# MiniDual_FanSpansion.net
KiCad netlist of a schematic drawn in EAGLE
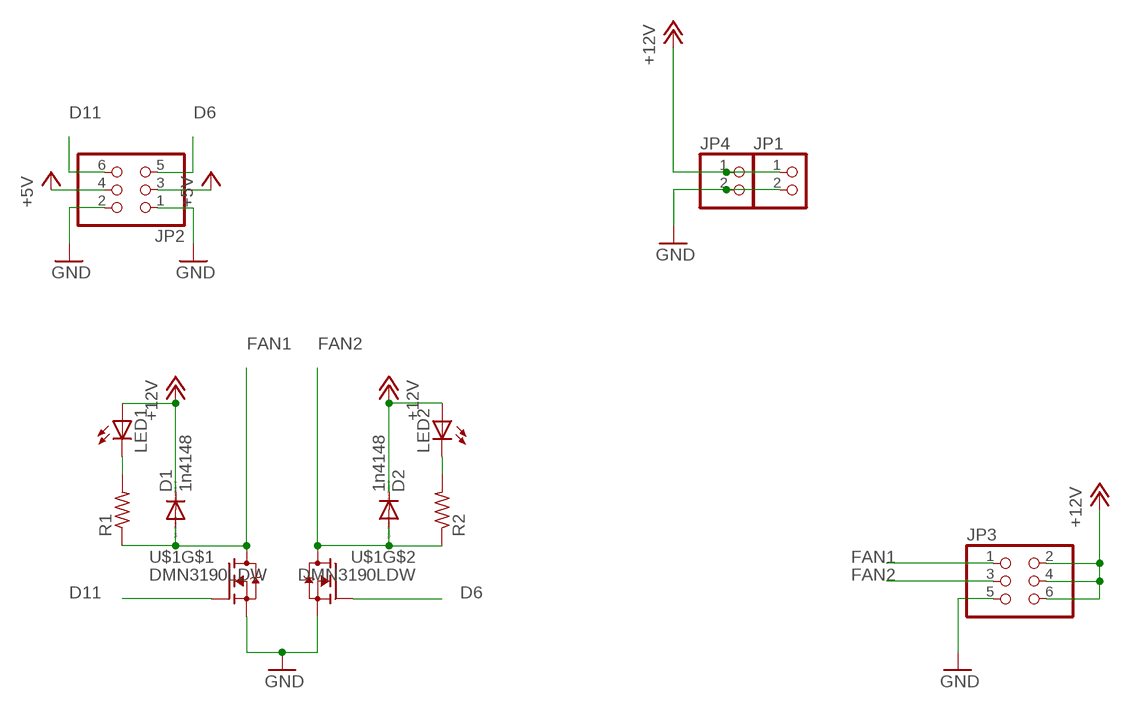
[diagram p0: schematic, sheet 1]

(export (version "E")
  (design (tool "Eeschema 10.0.6"))
  (components
    (comp (ref "D1")
      (value "1n4148")
      (footprint "eagle-import:SOD323-R")
      (libsource (lib "eagle-import") (part "DIODE-SOD323-R"))
    )
    (comp (ref "D2")
      (value "1n4148")
      (footprint "eagle-import:SOD323-R")
      (libsource (lib "eagle-import") (part "DIODE-SOD323-R"))
    )
    (comp (ref "JP1")
      (value "PINHD-1X2")
      (footprint "eagle-import:1X02")
      (libsource (lib "eagle-import") (part "PINHD-1X2"))
    )
    (comp (ref "JP2")
      (value "PINHD-2X3")
      (footprint "eagle-import:2X03")
      (libsource (lib "eagle-import") (part "PINHD-2X3"))
    )
    (comp (ref "JP3")
      (value "PINHD-2X3")
      (footprint "eagle-import:2X03")
      (libsource (lib "eagle-import") (part "PINHD-2X3"))
    )
    (comp (ref "JP4")
      (value "PINHD-1X2")
      (footprint "eagle-import:1X02")
      (libsource (lib "eagle-import") (part "PINHD-1X2"))
    )
    (comp (ref "LED1")
      (value "LEDSML0805")
      (footprint "eagle-import:SML0805")
      (libsource (lib "eagle-import") (part "LEDSML0805"))
    )
    (comp (ref "LED2")
      (value "LEDSML0805")
      (footprint "eagle-import:SML0805")
      (libsource (lib "eagle-import") (part "LEDSML0805"))
    )
    (comp (ref "R1")
      (value "R-US_R0805")
      (footprint "eagle-import:R0805")
      (libsource (lib "eagle-import") (part "R-US_R0805"))
    )
    (comp (ref "R2")
      (value "R-US_R0805")
      (footprint "eagle-import:R0805")
      (libsource (lib "eagle-import") (part "R-US_R0805"))
    )
    (comp (ref "U$1")
      (value "DMN3190LDW")
      (footprint "eagle-import:SOT65P210X110-6N")
      (libsource (lib "eagle-import") (part "DMN3190LDW"))
    )
  )
  (nets
    (net (code "1") (name "+5V") (class "Default")
      (node (ref "JP2") (pin "3") (pinfunction "3_3") (pintype "passive"))
      (node (ref "JP2") (pin "4") (pinfunction "4_4") (pintype "passive"))
    )
    (net (code "2") (name "+12V") (class "Default")
      (node (ref "D1") (pin "C") (pinfunction "C_C") (pintype "passive"))
      (node (ref "D2") (pin "C") (pinfunction "C_C") (pintype "passive"))
      (node (ref "JP1") (pin "1") (pinfunction "1_1") (pintype "passive"))
      (node (ref "JP3") (pin "2") (pinfunction "2_2") (pintype "passive"))
      (node (ref "JP3") (pin "4") (pinfunction "4_4") (pintype "passive"))
      (node (ref "JP3") (pin "6") (pinfunction "6_6") (pintype "passive"))
      (node (ref "JP4") (pin "1") (pinfunction "1_1") (pintype "passive"))
      (node (ref "LED1") (pin "A") (pinfunction "A_A") (pintype "passive"))
      (node (ref "LED2") (pin "A") (pinfunction "A_A") (pintype "passive"))
    )
    (net (code "3") (name "/D6") (class "Default")
      (node (ref "JP2") (pin "5") (pinfunction "5_5") (pintype "passive"))
      (node (ref "U$1") (pin "2") (pinfunction "G_2") (pintype "passive"))
    )
    (net (code "4") (name "/D11") (class "Default")
      (node (ref "JP2") (pin "6") (pinfunction "6_6") (pintype "passive"))
      (node (ref "U$1") (pin "5") (pinfunction "G_5") (pintype "passive"))
    )
    (net (code "5") (name "/FAN1") (class "Default")
      (node (ref "D1") (pin "A") (pinfunction "A_A") (pintype "passive"))
      (node (ref "JP3") (pin "1") (pinfunction "1_1") (pintype "passive"))
      (node (ref "R1") (pin "1") (pinfunction "1_1") (pintype "passive"))
      (node (ref "U$1") (pin "3") (pinfunction "D_3") (pintype "passive"))
    )
    (net (code "6") (name "/FAN2") (class "Default")
      (node (ref "D2") (pin "A") (pinfunction "A_A") (pintype "passive"))
      (node (ref "JP3") (pin "3") (pinfunction "3_3") (pintype "passive"))
      (node (ref "R2") (pin "1") (pinfunction "1_1") (pintype "passive"))
      (node (ref "U$1") (pin "6") (pinfunction "D_6") (pintype "passive"))
    )
    (net (code "7") (name "GND") (class "Default")
      (node (ref "JP1") (pin "2") (pinfunction "2_2") (pintype "passive"))
      (node (ref "JP2") (pin "1") (pinfunction "1_1") (pintype "passive"))
      (node (ref "JP2") (pin "2") (pinfunction "2_2") (pintype "passive"))
      (node (ref "JP3") (pin "5") (pinfunction "5_5") (pintype "passive"))
      (node (ref "JP4") (pin "2") (pinfunction "2_2") (pintype "passive"))
      (node (ref "U$1") (pin "1") (pinfunction "S_1") (pintype "passive"))
      (node (ref "U$1") (pin "4") (pinfunction "S_4") (pintype "passive"))
    )
    (net (code "8") (name "Net-(LED1-PadC)") (class "Default")
      (node (ref "LED1") (pin "C") (pinfunction "C_C") (pintype "passive"))
      (node (ref "R1") (pin "2") (pinfunction "2_2") (pintype "passive"))
    )
    (net (code "9") (name "Net-(LED2-PadC)") (class "Default")
      (node (ref "LED2") (pin "C") (pinfunction "C_C") (pintype "passive"))
      (node (ref "R2") (pin "2") (pinfunction "2_2") (pintype "passive"))
    )
  )
)
